# DDR2.net
KiCad netlist of a schematic drawn in Altium Designer
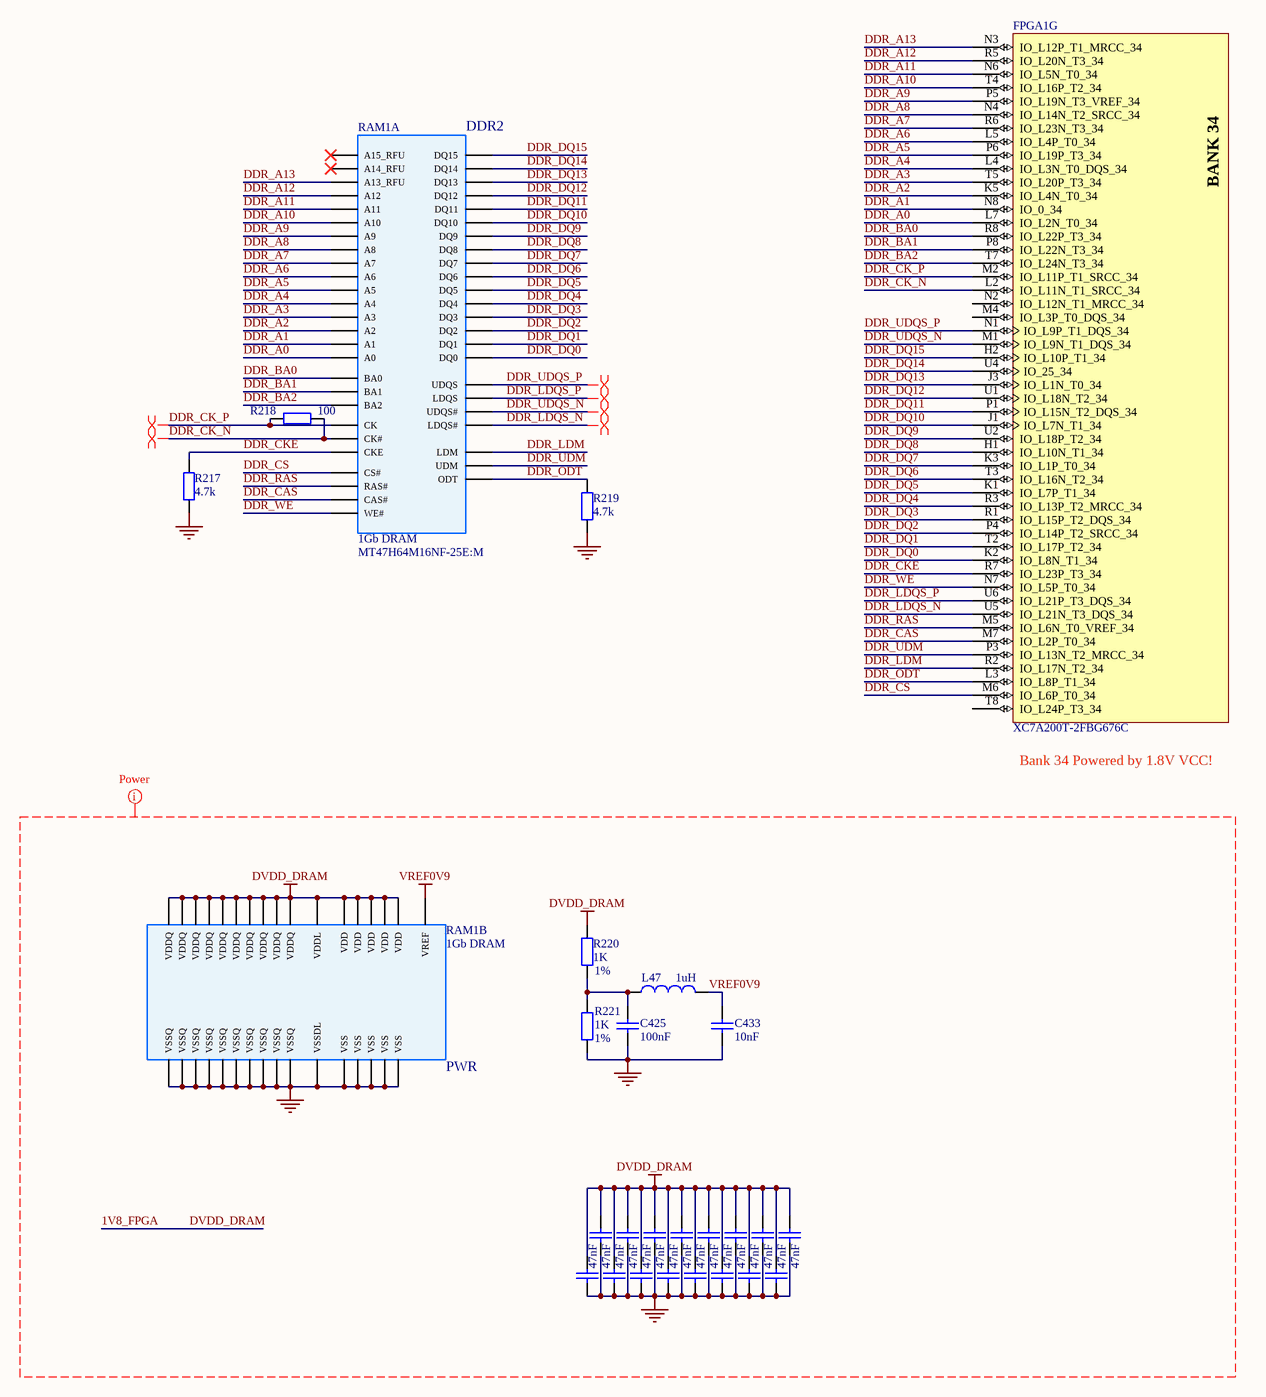
[diagram p0: DDR2.SchDoc]

(export (version "E")
  (design (tool "Eeschema 10.0.6"))
  (components
    (comp (ref "C422")
      (value "47nF")
      (footprint "С0402")
      (description "Cer Cap Small")
      (fields (field (name "MANUFACTURER") "Murata") (field (name "VOLTAGE") "50V"))
      (libsource (lib "USRP2_Clone") (part "Cer Cap"))
    )
    (comp (ref "C423")
      (value "47nF")
      (footprint "С0402")
      (description "Cer Cap Small")
      (fields (field (name "MANUFACTURER") "Murata") (field (name "VOLTAGE") "50V"))
      (libsource (lib "") (part "Cer Cap_1"))
    )
    (comp (ref "C424")
      (value "47nF")
      (footprint "С0402")
      (description "Cer Cap Small")
      (fields (field (name "MANUFACTURER") "Murata") (field (name "VOLTAGE") "50V"))
      (libsource (lib "USRP2_Clone") (part "Cer Cap"))
    )
    (comp (ref "C425")
      (value "100nF")
      (footprint "С0402")
      (description "Cer Cap Small")
      (fields (field (name "MANUFACTURER") "Murata") (field (name "VOLTAGE") "50V"))
      (libsource (lib "") (part "Cer Cap_1"))
    )
    (comp (ref "C426")
      (value "47nF")
      (footprint "С0402")
      (description "Cer Cap Small")
      (fields (field (name "MANUFACTURER") "Murata") (field (name "VOLTAGE") "50V"))
      (libsource (lib "USRP2_Clone") (part "Cer Cap"))
    )
    (comp (ref "C427")
      (value "47nF")
      (footprint "С0402")
      (description "Cer Cap Small")
      (fields (field (name "MANUFACTURER") "Murata") (field (name "VOLTAGE") "50V"))
      (libsource (lib "USRP2_Clone") (part "Cer Cap"))
    )
    (comp (ref "C428")
      (value "47nF")
      (footprint "С0402")
      (description "Cer Cap Small")
      (fields (field (name "MANUFACTURER") "Murata") (field (name "VOLTAGE") "50V"))
      (libsource (lib "") (part "Cer Cap_1"))
    )
    (comp (ref "C429")
      (value "47nF")
      (footprint "С0402")
      (description "Cer Cap Small")
      (fields (field (name "MANUFACTURER") "Murata") (field (name "VOLTAGE") "50V"))
      (libsource (lib "") (part "Cer Cap_1"))
    )
    (comp (ref "C430")
      (value "47nF")
      (footprint "С0402")
      (description "Cer Cap Small")
      (fields (field (name "MANUFACTURER") "Murata") (field (name "VOLTAGE") "50V"))
      (libsource (lib "") (part "Cer Cap_1"))
    )
    (comp (ref "C431")
      (value "47nF")
      (footprint "С0402")
      (description "Cer Cap Small")
      (fields (field (name "MANUFACTURER") "Murata") (field (name "VOLTAGE") "50V"))
      (libsource (lib "USRP2_Clone") (part "Cer Cap"))
    )
    (comp (ref "C432")
      (value "47nF")
      (footprint "С0402")
      (description "Cer Cap Small")
      (fields (field (name "MANUFACTURER") "Murata") (field (name "VOLTAGE") "50V"))
      (libsource (lib "USRP2_Clone") (part "Cer Cap"))
    )
    (comp (ref "C433")
      (value "10nF")
      (footprint "С0402")
      (description "Cer Cap Small")
      (fields (field (name "MANUFACTURER") "Murata") (field (name "VOLTAGE") "50V"))
      (libsource (lib "") (part "Cer Cap_1"))
    )
    (comp (ref "C434")
      (value "47nF")
      (footprint "С0402")
      (description "Cer Cap Small")
      (fields (field (name "MANUFACTURER") "Murata") (field (name "VOLTAGE") "50V"))
      (libsource (lib "USRP2_Clone") (part "Cer Cap"))
    )
    (comp (ref "C435")
      (value "47nF")
      (footprint "С0402")
      (description "Cer Cap Small")
      (fields (field (name "MANUFACTURER") "Murata") (field (name "VOLTAGE") "50V"))
      (libsource (lib "") (part "Cer Cap_1"))
    )
    (comp (ref "C436")
      (value "47nF")
      (footprint "С0402")
      (description "Cer Cap Small")
      (fields (field (name "MANUFACTURER") "Murata") (field (name "VOLTAGE") "50V"))
      (libsource (lib "USRP2_Clone") (part "Cer Cap"))
    )
    (comp (ref "C437")
      (value "47nF")
      (footprint "С0402")
      (description "Cer Cap Small")
      (fields (field (name "MANUFACTURER") "Murata") (field (name "VOLTAGE") "50V"))
      (libsource (lib "USRP2_Clone") (part "Cer Cap"))
    )
    (comp (ref "C438")
      (value "47nF")
      (footprint "С0402")
      (description "Cer Cap Small")
      (fields (field (name "MANUFACTURER") "Murata") (field (name "VOLTAGE") "50V"))
      (libsource (lib "USRP2_Clone") (part "Cer Cap"))
    )
    (comp (ref "C439")
      (value "47nF")
      (footprint "С0402")
      (description "Cer Cap Small")
      (fields (field (name "MANUFACTURER") "Murata") (field (name "VOLTAGE") "50V"))
      (libsource (lib "") (part "Cer Cap_1"))
    )
    (comp (ref "FPGA1")
      (value "XC7A200T-2FBG676C")
      (footprint "FGG676")
      (description "Artix-7 FPGA, 400 User I/Os, 8 GTP, 676-Ball BGA, Speed Grade 2, Commercial Grade, Pb-Free")
      (fields (field (name "GENERIC PART NUMBER") "XC7A200T") (field (name "MANUFACTURER") "Xilinx"))
      (libsource (lib "USRP2_Clone") (part "XC7A200T-2FBG676C"))
    )
    (comp (ref "L47")
      (value "1uH")
      (footprint "L1206_Murata")
      (description "Inductor_Power_Lines")
      (fields (field (name "TOLERANCE") "5%") (field (name "MANUFACTURER") "Murata"))
      (libsource (lib "USRP2_Clone") (part "Inductor_LF"))
    )
    (comp (ref "R217")
      (value "4.7k")
      (footprint "R0402")
      (description "Resistor")
      (fields (field (name "TOLERANCE") "5%") (field (name "POWER") "0.062 Wt"))
      (libsource (lib "USRP2_Clone") (part "Res"))
    )
    (comp (ref "R218")
      (value "100")
      (footprint "R0402")
      (description "Resistor")
      (fields (field (name "TOLERANCE") "5%") (field (name "POWER") "0.062 Wt"))
      (libsource (lib "") (part "Res_2"))
    )
    (comp (ref "R219")
      (value "4.7k")
      (footprint "R0402")
      (description "Resistor")
      (fields (field (name "TOLERANCE") "5%") (field (name "POWER") "0.062 Wt"))
      (libsource (lib "USRP2_Clone") (part "Res"))
    )
    (comp (ref "R220")
      (value "1K")
      (footprint "R0402")
      (description "Resistor")
      (fields
        (field (name "TOLERANCE") "1%")
        (field (name "POWER") "0.062 Wt")
        (field (name "Comment") "Res")
      )
      (libsource (lib "USRP2_Clone") (part "Res"))
    )
    (comp (ref "R221")
      (value "1K")
      (footprint "R0402")
      (description "Resistor")
      (fields
        (field (name "TOLERANCE") "1%")
        (field (name "POWER") "0.062 Wt")
        (field (name "Comment") "Res")
      )
      (libsource (lib "") (part "Res_1"))
    )
    (comp (ref "RAM1")
      (value "1Gb DRAM")
      (footprint "BGA84")
      (description "DDR2 1Gb DRAM")
      (fields
        (field (name "MANUFACTURER") "Micron Technology Inc.")
        (field (name "VOLTAGE") "V  DD  = 1.8V ±0.1V, V  DDQ  = 1.8V ±0.1V")
        (field (name "NAME") "MT47H64M16NF-25E:M")
      )
      (libsource (lib "USRP2_Clone") (part "MT47H64M16"))
    )
  )
  (nets
    (net (code "1") (name "/DDR_A0") (class "Default")
      (node (ref "FPGA1") (pin "L7") (pinfunction "IO_L2N_T0_34_L7") (pintype "bidirectional"))
      (node (ref "RAM1") (pin "M8") (pinfunction "A0_M8") (pintype "passive"))
    )
    (net (code "2") (name "/DDR_A1") (class "Default")
      (node (ref "FPGA1") (pin "N8") (pinfunction "IO_0_34_N8") (pintype "bidirectional"))
      (node (ref "RAM1") (pin "M3") (pinfunction "A1_M3") (pintype "passive"))
    )
    (net (code "3") (name "/DDR_A2") (class "Default")
      (node (ref "FPGA1") (pin "K5") (pinfunction "IO_L4N_T0_34_K5") (pintype "bidirectional"))
      (node (ref "RAM1") (pin "M7") (pinfunction "A2_M7") (pintype "passive"))
    )
    (net (code "4") (name "/DDR_A3") (class "Default")
      (node (ref "FPGA1") (pin "T5") (pinfunction "IO_L20P_T3_34_T5") (pintype "bidirectional"))
      (node (ref "RAM1") (pin "N2") (pinfunction "A3_N2") (pintype "passive"))
    )
    (net (code "5") (name "/DDR_A4") (class "Default")
      (node (ref "FPGA1") (pin "L4") (pinfunction "IO_L3N_T0_DQS_34_L4") (pintype "bidirectional"))
      (node (ref "RAM1") (pin "N8") (pinfunction "A4_N8") (pintype "passive"))
    )
    (net (code "6") (name "/DDR_A5") (class "Default")
      (node (ref "FPGA1") (pin "P6") (pinfunction "IO_L19P_T3_34_P6") (pintype "bidirectional"))
      (node (ref "RAM1") (pin "N3") (pinfunction "A5_N3") (pintype "passive"))
    )
    (net (code "7") (name "/DDR_A6") (class "Default")
      (node (ref "FPGA1") (pin "L5") (pinfunction "IO_L4P_T0_34_L5") (pintype "bidirectional"))
      (node (ref "RAM1") (pin "N7") (pinfunction "A6_N7") (pintype "passive"))
    )
    (net (code "8") (name "/DDR_A7") (class "Default")
      (node (ref "FPGA1") (pin "R6") (pinfunction "IO_L23N_T3_34_R6") (pintype "bidirectional"))
      (node (ref "RAM1") (pin "P2") (pinfunction "A7_P2") (pintype "passive"))
    )
    (net (code "9") (name "/DDR_A8") (class "Default")
      (node (ref "FPGA1") (pin "N4") (pinfunction "IO_L14N_T2_SRCC_34_N4") (pintype "bidirectional"))
      (node (ref "RAM1") (pin "P8") (pinfunction "A8_P8") (pintype "passive"))
    )
    (net (code "10") (name "/DDR_A9") (class "Default")
      (node (ref "FPGA1") (pin "P5") (pinfunction "IO_L19N_T3_VREF_34_P5") (pintype "bidirectional"))
      (node (ref "RAM1") (pin "P3") (pinfunction "A9_P3") (pintype "passive"))
    )
    (net (code "11") (name "/DDR_A10") (class "Default")
      (node (ref "FPGA1") (pin "T4") (pinfunction "IO_L16P_T2_34_T4") (pintype "bidirectional"))
      (node (ref "RAM1") (pin "M2") (pinfunction "A10_M2") (pintype "passive"))
    )
    (net (code "12") (name "/DDR_A11") (class "Default")
      (node (ref "FPGA1") (pin "N6") (pinfunction "IO_L5N_T0_34_N6") (pintype "bidirectional"))
      (node (ref "RAM1") (pin "P7") (pinfunction "A11_P7") (pintype "passive"))
    )
    (net (code "13") (name "/DDR_A12") (class "Default")
      (node (ref "FPGA1") (pin "R5") (pinfunction "IO_L20N_T3_34_R5") (pintype "bidirectional"))
      (node (ref "RAM1") (pin "R2") (pinfunction "A12_R2") (pintype "passive"))
    )
    (net (code "14") (name "/DDR_A13") (class "Default")
      (node (ref "FPGA1") (pin "N3") (pinfunction "IO_L12P_T1_MRCC_34_N3") (pintype "bidirectional"))
      (node (ref "RAM1") (pin "R8") (pinfunction "A13_RFU_R8") (pintype "passive"))
    )
    (net (code "15") (name "/DDR_BA0") (class "Default")
      (node (ref "FPGA1") (pin "R8") (pinfunction "IO_L22P_T3_34_R8") (pintype "bidirectional"))
      (node (ref "RAM1") (pin "L2") (pinfunction "BA0_L2") (pintype "passive"))
    )
    (net (code "16") (name "/DDR_BA1") (class "Default")
      (node (ref "FPGA1") (pin "P8") (pinfunction "IO_L22N_T3_34_P8") (pintype "bidirectional"))
      (node (ref "RAM1") (pin "L3") (pinfunction "BA1_L3") (pintype "passive"))
    )
    (net (code "17") (name "/DDR_BA2") (class "Default")
      (node (ref "FPGA1") (pin "T7") (pinfunction "IO_L24N_T3_34_T7") (pintype "bidirectional"))
      (node (ref "RAM1") (pin "L1") (pinfunction "BA2_L1") (pintype "passive"))
    )
    (net (code "18") (name "/DDR_CAS") (class "Default")
      (node (ref "FPGA1") (pin "M7") (pinfunction "IO_L2P_T0_34_M7") (pintype "bidirectional"))
      (node (ref "RAM1") (pin "L7") (pinfunction "CAS#_L7") (pintype "passive"))
    )
    (net (code "19") (name "/DDR_CKE") (class "Default")
      (node (ref "FPGA1") (pin "R7") (pinfunction "IO_L23P_T3_34_R7") (pintype "bidirectional"))
      (node (ref "R217") (pin "2") (pinfunction "2_2") (pintype "passive"))
      (node (ref "RAM1") (pin "K2") (pinfunction "CKE_K2") (pintype "passive"))
    )
    (net (code "20") (name "/DDR_CK_N") (class "Default")
      (node (ref "FPGA1") (pin "L2") (pinfunction "IO_L11N_T1_SRCC_34_L2") (pintype "bidirectional"))
      (node (ref "R218") (pin "2") (pinfunction "2_2") (pintype "passive"))
      (node (ref "RAM1") (pin "K8") (pinfunction "CK#_K8") (pintype "passive"))
    )
    (net (code "21") (name "/DDR_CK_P") (class "Default")
      (node (ref "FPGA1") (pin "M2") (pinfunction "IO_L11P_T1_SRCC_34_M2") (pintype "bidirectional"))
      (node (ref "R218") (pin "1") (pinfunction "1_1") (pintype "passive"))
      (node (ref "RAM1") (pin "J8") (pinfunction "CK_J8") (pintype "passive"))
    )
    (net (code "22") (name "/DDR_CS") (class "Default")
      (node (ref "FPGA1") (pin "M6") (pinfunction "IO_L6P_T0_34_M6") (pintype "bidirectional"))
      (node (ref "RAM1") (pin "L8") (pinfunction "CS#_L8") (pintype "passive"))
    )
    (net (code "23") (name "/DDR_DQ0") (class "Default")
      (node (ref "FPGA1") (pin "K2") (pinfunction "IO_L8N_T1_34_K2") (pintype "bidirectional"))
      (node (ref "RAM1") (pin "G8") (pinfunction "DQ0_G8") (pintype "passive"))
    )
    (net (code "24") (name "/DDR_DQ1") (class "Default")
      (node (ref "FPGA1") (pin "T2") (pinfunction "IO_L17P_T2_34_T2") (pintype "bidirectional"))
      (node (ref "RAM1") (pin "G2") (pinfunction "DQ1_G2") (pintype "passive"))
    )
    (net (code "25") (name "/DDR_DQ2") (class "Default")
      (node (ref "FPGA1") (pin "P4") (pinfunction "IO_L14P_T2_SRCC_34_P4") (pintype "bidirectional"))
      (node (ref "RAM1") (pin "H7") (pinfunction "DQ2_H7") (pintype "passive"))
    )
    (net (code "26") (name "/DDR_DQ3") (class "Default")
      (node (ref "FPGA1") (pin "R1") (pinfunction "IO_L15P_T2_DQS_34_R1") (pintype "bidirectional"))
      (node (ref "RAM1") (pin "H3") (pinfunction "DQ3_H3") (pintype "passive"))
    )
    (net (code "27") (name "/DDR_DQ4") (class "Default")
      (node (ref "FPGA1") (pin "R3") (pinfunction "IO_L13P_T2_MRCC_34_R3") (pintype "bidirectional"))
      (node (ref "RAM1") (pin "H1") (pinfunction "DQ4_H1") (pintype "passive"))
    )
    (net (code "28") (name "/DDR_DQ5") (class "Default")
      (node (ref "FPGA1") (pin "K1") (pinfunction "IO_L7P_T1_34_K1") (pintype "bidirectional"))
      (node (ref "RAM1") (pin "H9") (pinfunction "DQ5_H9") (pintype "passive"))
    )
    (net (code "29") (name "/DDR_DQ6") (class "Default")
      (node (ref "FPGA1") (pin "T3") (pinfunction "IO_L16N_T2_34_T3") (pintype "bidirectional"))
      (node (ref "RAM1") (pin "F1") (pinfunction "DQ6_F1") (pintype "passive"))
    )
    (net (code "30") (name "/DDR_DQ7") (class "Default")
      (node (ref "FPGA1") (pin "K3") (pinfunction "IO_L1P_T0_34_K3") (pintype "bidirectional"))
      (node (ref "RAM1") (pin "F9") (pinfunction "DQ7_F9") (pintype "passive"))
    )
    (net (code "31") (name "/DDR_DQ8") (class "Default")
      (node (ref "FPGA1") (pin "H1") (pinfunction "IO_L10N_T1_34_H1") (pintype "bidirectional"))
      (node (ref "RAM1") (pin "C8") (pinfunction "DQ8_C8") (pintype "passive"))
    )
    (net (code "32") (name "/DDR_DQ9") (class "Default")
      (node (ref "FPGA1") (pin "U2") (pinfunction "IO_L18P_T2_34_U2") (pintype "bidirectional"))
      (node (ref "RAM1") (pin "C2") (pinfunction "DQ9_C2") (pintype "passive"))
    )
    (net (code "33") (name "/DDR_DQ10") (class "Default")
      (node (ref "FPGA1") (pin "J1") (pinfunction "IO_L7N_T1_34_J1") (pintype "bidirectional"))
      (node (ref "RAM1") (pin "D7") (pinfunction "DQ10_D7") (pintype "passive"))
    )
    (net (code "34") (name "/DDR_DQ11") (class "Default")
      (node (ref "FPGA1") (pin "P1") (pinfunction "IO_L15N_T2_DQS_34_P1") (pintype "bidirectional"))
      (node (ref "RAM1") (pin "D3") (pinfunction "DQ11_D3") (pintype "passive"))
    )
    (net (code "35") (name "/DDR_DQ12") (class "Default")
      (node (ref "FPGA1") (pin "U1") (pinfunction "IO_L18N_T2_34_U1") (pintype "bidirectional"))
      (node (ref "RAM1") (pin "D1") (pinfunction "DQ12_D1") (pintype "passive"))
    )
    (net (code "36") (name "/DDR_DQ13") (class "Default")
      (node (ref "FPGA1") (pin "J3") (pinfunction "IO_L1N_T0_34_J3") (pintype "bidirectional"))
      (node (ref "RAM1") (pin "D9") (pinfunction "DQ13_D9") (pintype "passive"))
    )
    (net (code "37") (name "/DDR_DQ14") (class "Default")
      (node (ref "FPGA1") (pin "U4") (pinfunction "IO_25_34_U4") (pintype "bidirectional"))
      (node (ref "RAM1") (pin "B1") (pinfunction "DQ14_B1") (pintype "passive"))
    )
    (net (code "38") (name "/DDR_DQ15") (class "Default")
      (node (ref "FPGA1") (pin "H2") (pinfunction "IO_L10P_T1_34_H2") (pintype "bidirectional"))
      (node (ref "RAM1") (pin "B9") (pinfunction "DQ15_B9") (pintype "passive"))
    )
    (net (code "39") (name "/DDR_LDM") (class "Default")
      (node (ref "FPGA1") (pin "R2") (pinfunction "IO_L17N_T2_34_R2") (pintype "bidirectional"))
      (node (ref "RAM1") (pin "F3") (pinfunction "LDM_F3") (pintype "passive"))
    )
    (net (code "40") (name "/DDR_LDQS_N") (class "Default")
      (node (ref "FPGA1") (pin "U5") (pinfunction "IO_L21N_T3_DQS_34_U5") (pintype "bidirectional"))
      (node (ref "RAM1") (pin "E8") (pinfunction "LDQS#_E8") (pintype "passive"))
    )
    (net (code "41") (name "/DDR_LDQS_P") (class "Default")
      (node (ref "FPGA1") (pin "U6") (pinfunction "IO_L21P_T3_DQS_34_U6") (pintype "bidirectional"))
      (node (ref "RAM1") (pin "F7") (pinfunction "LDQS_F7") (pintype "passive"))
    )
    (net (code "42") (name "/DDR_ODT") (class "Default")
      (node (ref "FPGA1") (pin "L3") (pinfunction "IO_L8P_T1_34_L3") (pintype "bidirectional"))
      (node (ref "R219") (pin "2") (pinfunction "2_2") (pintype "passive"))
      (node (ref "RAM1") (pin "K9") (pinfunction "ODT_K9") (pintype "passive"))
    )
    (net (code "43") (name "/DDR_RAS") (class "Default")
      (node (ref "FPGA1") (pin "M5") (pinfunction "IO_L6N_T0_VREF_34_M5") (pintype "bidirectional"))
      (node (ref "RAM1") (pin "K7") (pinfunction "RAS#_K7") (pintype "passive"))
    )
    (net (code "44") (name "/DDR_UDM") (class "Default")
      (node (ref "FPGA1") (pin "P3") (pinfunction "IO_L13N_T2_MRCC_34_P3") (pintype "bidirectional"))
      (node (ref "RAM1") (pin "B3") (pinfunction "UDM_B3") (pintype "passive"))
    )
    (net (code "45") (name "/DDR_UDQS_N") (class "Default")
      (node (ref "FPGA1") (pin "M1") (pinfunction "IO_L9N_T1_DQS_34_M1") (pintype "bidirectional"))
      (node (ref "RAM1") (pin "A8") (pinfunction "UDQS#_A8") (pintype "passive"))
    )
    (net (code "46") (name "/DDR_UDQS_P") (class "Default")
      (node (ref "FPGA1") (pin "N1") (pinfunction "IO_L9P_T1_DQS_34_N1") (pintype "bidirectional"))
      (node (ref "RAM1") (pin "B7") (pinfunction "UDQS_B7") (pintype "passive"))
    )
    (net (code "47") (name "/DDR_WE") (class "Default")
      (node (ref "FPGA1") (pin "N7") (pinfunction "IO_L5P_T0_34_N7") (pintype "bidirectional"))
      (node (ref "RAM1") (pin "K3") (pinfunction "WE#_K3") (pintype "passive"))
    )
    (net (code "48") (name "DVDD_DRAM") (class "Default")
      (node (ref "C422") (pin "2") (pinfunction "2_2") (pintype "passive"))
      (node (ref "C423") (pin "1") (pinfunction "1_1") (pintype "passive"))
      (node (ref "C424") (pin "2") (pinfunction "2_2") (pintype "passive"))
      (node (ref "C426") (pin "2") (pinfunction "2_2") (pintype "passive"))
      (node (ref "C427") (pin "2") (pinfunction "2_2") (pintype "passive"))
      (node (ref "C428") (pin "1") (pinfunction "1_1") (pintype "passive"))
      (node (ref "C429") (pin "1") (pinfunction "1_1") (pintype "passive"))
      (node (ref "C430") (pin "1") (pinfunction "1_1") (pintype "passive"))
      (node (ref "C431") (pin "2") (pinfunction "2_2") (pintype "passive"))
      (node (ref "C432") (pin "2") (pinfunction "2_2") (pintype "passive"))
      (node (ref "C434") (pin "2") (pinfunction "2_2") (pintype "passive"))
      (node (ref "C435") (pin "1") (pinfunction "1_1") (pintype "passive"))
      (node (ref "C436") (pin "2") (pinfunction "2_2") (pintype "passive"))
      (node (ref "C437") (pin "2") (pinfunction "2_2") (pintype "passive"))
      (node (ref "C438") (pin "2") (pinfunction "2_2") (pintype "passive"))
      (node (ref "C439") (pin "1") (pinfunction "1_1") (pintype "passive"))
      (node (ref "R220") (pin "2") (pinfunction "2_2") (pintype "passive"))
      (node (ref "RAM1") (pin "A1") (pinfunction "VDD_A1") (pintype "passive"))
      (node (ref "RAM1") (pin "A9") (pinfunction "VDDQ_A9") (pintype "passive"))
      (node (ref "RAM1") (pin "C1") (pinfunction "VDDQ_C1") (pintype "passive"))
      (node (ref "RAM1") (pin "C3") (pinfunction "VDDQ_C3") (pintype "passive"))
      (node (ref "RAM1") (pin "C7") (pinfunction "VDDQ_C7") (pintype "passive"))
      (node (ref "RAM1") (pin "C9") (pinfunction "VDDQ_C9") (pintype "passive"))
      (node (ref "RAM1") (pin "E1") (pinfunction "VDD_E1") (pintype "passive"))
      (node (ref "RAM1") (pin "E9") (pinfunction "VDDQ_E9") (pintype "passive"))
      (node (ref "RAM1") (pin "G1") (pinfunction "VDDQ_G1") (pintype "passive"))
      (node (ref "RAM1") (pin "G3") (pinfunction "VDDQ_G3") (pintype "passive"))
      (node (ref "RAM1") (pin "G7") (pinfunction "VDDQ_G7") (pintype "passive"))
      (node (ref "RAM1") (pin "G9") (pinfunction "VDDQ_G9") (pintype "passive"))
      (node (ref "RAM1") (pin "J1") (pinfunction "VDDL_J1") (pintype "passive"))
      (node (ref "RAM1") (pin "J9") (pinfunction "VDD_J9") (pintype "passive"))
      (node (ref "RAM1") (pin "M9") (pinfunction "VDD_M9") (pintype "passive"))
      (node (ref "RAM1") (pin "R1") (pinfunction "VDD_R1") (pintype "passive"))
    )
    (net (code "49") (name "GND") (class "Default")
      (node (ref "C422") (pin "1") (pinfunction "1_1") (pintype "passive"))
      (node (ref "C423") (pin "2") (pinfunction "2_2") (pintype "passive"))
      (node (ref "C424") (pin "1") (pinfunction "1_1") (pintype "passive"))
      (node (ref "C425") (pin "2") (pinfunction "2_2") (pintype "passive"))
      (node (ref "C426") (pin "1") (pinfunction "1_1") (pintype "passive"))
      (node (ref "C427") (pin "1") (pinfunction "1_1") (pintype "passive"))
      (node (ref "C428") (pin "2") (pinfunction "2_2") (pintype "passive"))
      (node (ref "C429") (pin "2") (pinfunction "2_2") (pintype "passive"))
      (node (ref "C430") (pin "2") (pinfunction "2_2") (pintype "passive"))
      (node (ref "C431") (pin "1") (pinfunction "1_1") (pintype "passive"))
      (node (ref "C432") (pin "1") (pinfunction "1_1") (pintype "passive"))
      (node (ref "C433") (pin "1") (pinfunction "1_1") (pintype "passive"))
      (node (ref "C434") (pin "1") (pinfunction "1_1") (pintype "passive"))
      (node (ref "C435") (pin "2") (pinfunction "2_2") (pintype "passive"))
      (node (ref "C436") (pin "1") (pinfunction "1_1") (pintype "passive"))
      (node (ref "C437") (pin "1") (pinfunction "1_1") (pintype "passive"))
      (node (ref "C438") (pin "1") (pinfunction "1_1") (pintype "passive"))
      (node (ref "C439") (pin "2") (pinfunction "2_2") (pintype "passive"))
      (node (ref "R217") (pin "1") (pinfunction "1_1") (pintype "passive"))
      (node (ref "R219") (pin "1") (pinfunction "1_1") (pintype "passive"))
      (node (ref "R221") (pin "2") (pinfunction "2_2") (pintype "passive"))
      (node (ref "RAM1") (pin "A3") (pinfunction "VSS_A3") (pintype "passive"))
      (node (ref "RAM1") (pin "A7") (pinfunction "VSSQ_A7") (pintype "passive"))
      (node (ref "RAM1") (pin "B2") (pinfunction "VSSQ_B2") (pintype "passive"))
      (node (ref "RAM1") (pin "B8") (pinfunction "VSSQ_B8") (pintype "passive"))
      (node (ref "RAM1") (pin "D2") (pinfunction "VSSQ_D2") (pintype "passive"))
      (node (ref "RAM1") (pin "D8") (pinfunction "VSSQ_D8") (pintype "passive"))
      (node (ref "RAM1") (pin "E3") (pinfunction "VSS_E3") (pintype "passive"))
      (node (ref "RAM1") (pin "E7") (pinfunction "VSSQ_E7") (pintype "passive"))
      (node (ref "RAM1") (pin "F2") (pinfunction "VSSQ_F2") (pintype "passive"))
      (node (ref "RAM1") (pin "F8") (pinfunction "VSSQ_F8") (pintype "passive"))
      (node (ref "RAM1") (pin "H2") (pinfunction "VSSQ_H2") (pintype "passive"))
      (node (ref "RAM1") (pin "H8") (pinfunction "VSSQ_H8") (pintype "passive"))
      (node (ref "RAM1") (pin "J3") (pinfunction "VSS_J3") (pintype "passive"))
      (node (ref "RAM1") (pin "J7") (pinfunction "VSSDL_J7") (pintype "passive"))
      (node (ref "RAM1") (pin "N1") (pinfunction "VSS_N1") (pintype "passive"))
      (node (ref "RAM1") (pin "P9") (pinfunction "VSS_P9") (pintype "passive"))
    )
    (net (code "50") (name "Net-(C425-Pad1)") (class "Default")
      (node (ref "C425") (pin "1") (pinfunction "1_1") (pintype "passive"))
      (node (ref "L47") (pin "2") (pinfunction "2_2") (pintype "passive"))
      (node (ref "R220") (pin "1") (pinfunction "1_1") (pintype "passive"))
      (node (ref "R221") (pin "1") (pinfunction "1_1") (pintype "passive"))
    )
    (net (code "51") (name "VREF0V9") (class "Default")
      (node (ref "C433") (pin "2") (pinfunction "2_2") (pintype "passive"))
      (node (ref "L47") (pin "1") (pinfunction "1_1") (pintype "passive"))
      (node (ref "RAM1") (pin "J2") (pinfunction "VREF_J2") (pintype "passive"))
    )
    (net (code "52") (name "unconnected-(FPGA1G-IO_L3P_T0_DQS_34-PadM4)") (class "Default")
      (node (ref "FPGA1") (pin "M4") (pinfunction "IO_L3P_T0_DQS_34_M4") (pintype "bidirectional"))
    )
    (net (code "53") (name "unconnected-(FPGA1G-IO_L12N_T1_MRCC_34-PadN2)") (class "Default")
      (node (ref "FPGA1") (pin "N2") (pinfunction "IO_L12N_T1_MRCC_34_N2") (pintype "bidirectional"))
    )
    (net (code "54") (name "unconnected-(FPGA1G-IO_L24P_T3_34-PadT8)") (class "Default")
      (node (ref "FPGA1") (pin "T8") (pinfunction "IO_L24P_T3_34_T8") (pintype "bidirectional"))
    )
    (net (code "55") (name "unconnected-(RAM1A-A14_RFU-PadR3)") (class "Default")
      (node (ref "RAM1") (pin "R3") (pinfunction "A14_RFU_R3") (pintype "passive+no_connect"))
    )
    (net (code "56") (name "unconnected-(RAM1A-A15_RFU-PadR7)") (class "Default")
      (node (ref "RAM1") (pin "R7") (pinfunction "A15_RFU_R7") (pintype "passive+no_connect"))
    )
  )
)
